# TH8_TEC_driver.net
KiCad netlist of a schematic drawn in Altium Designer
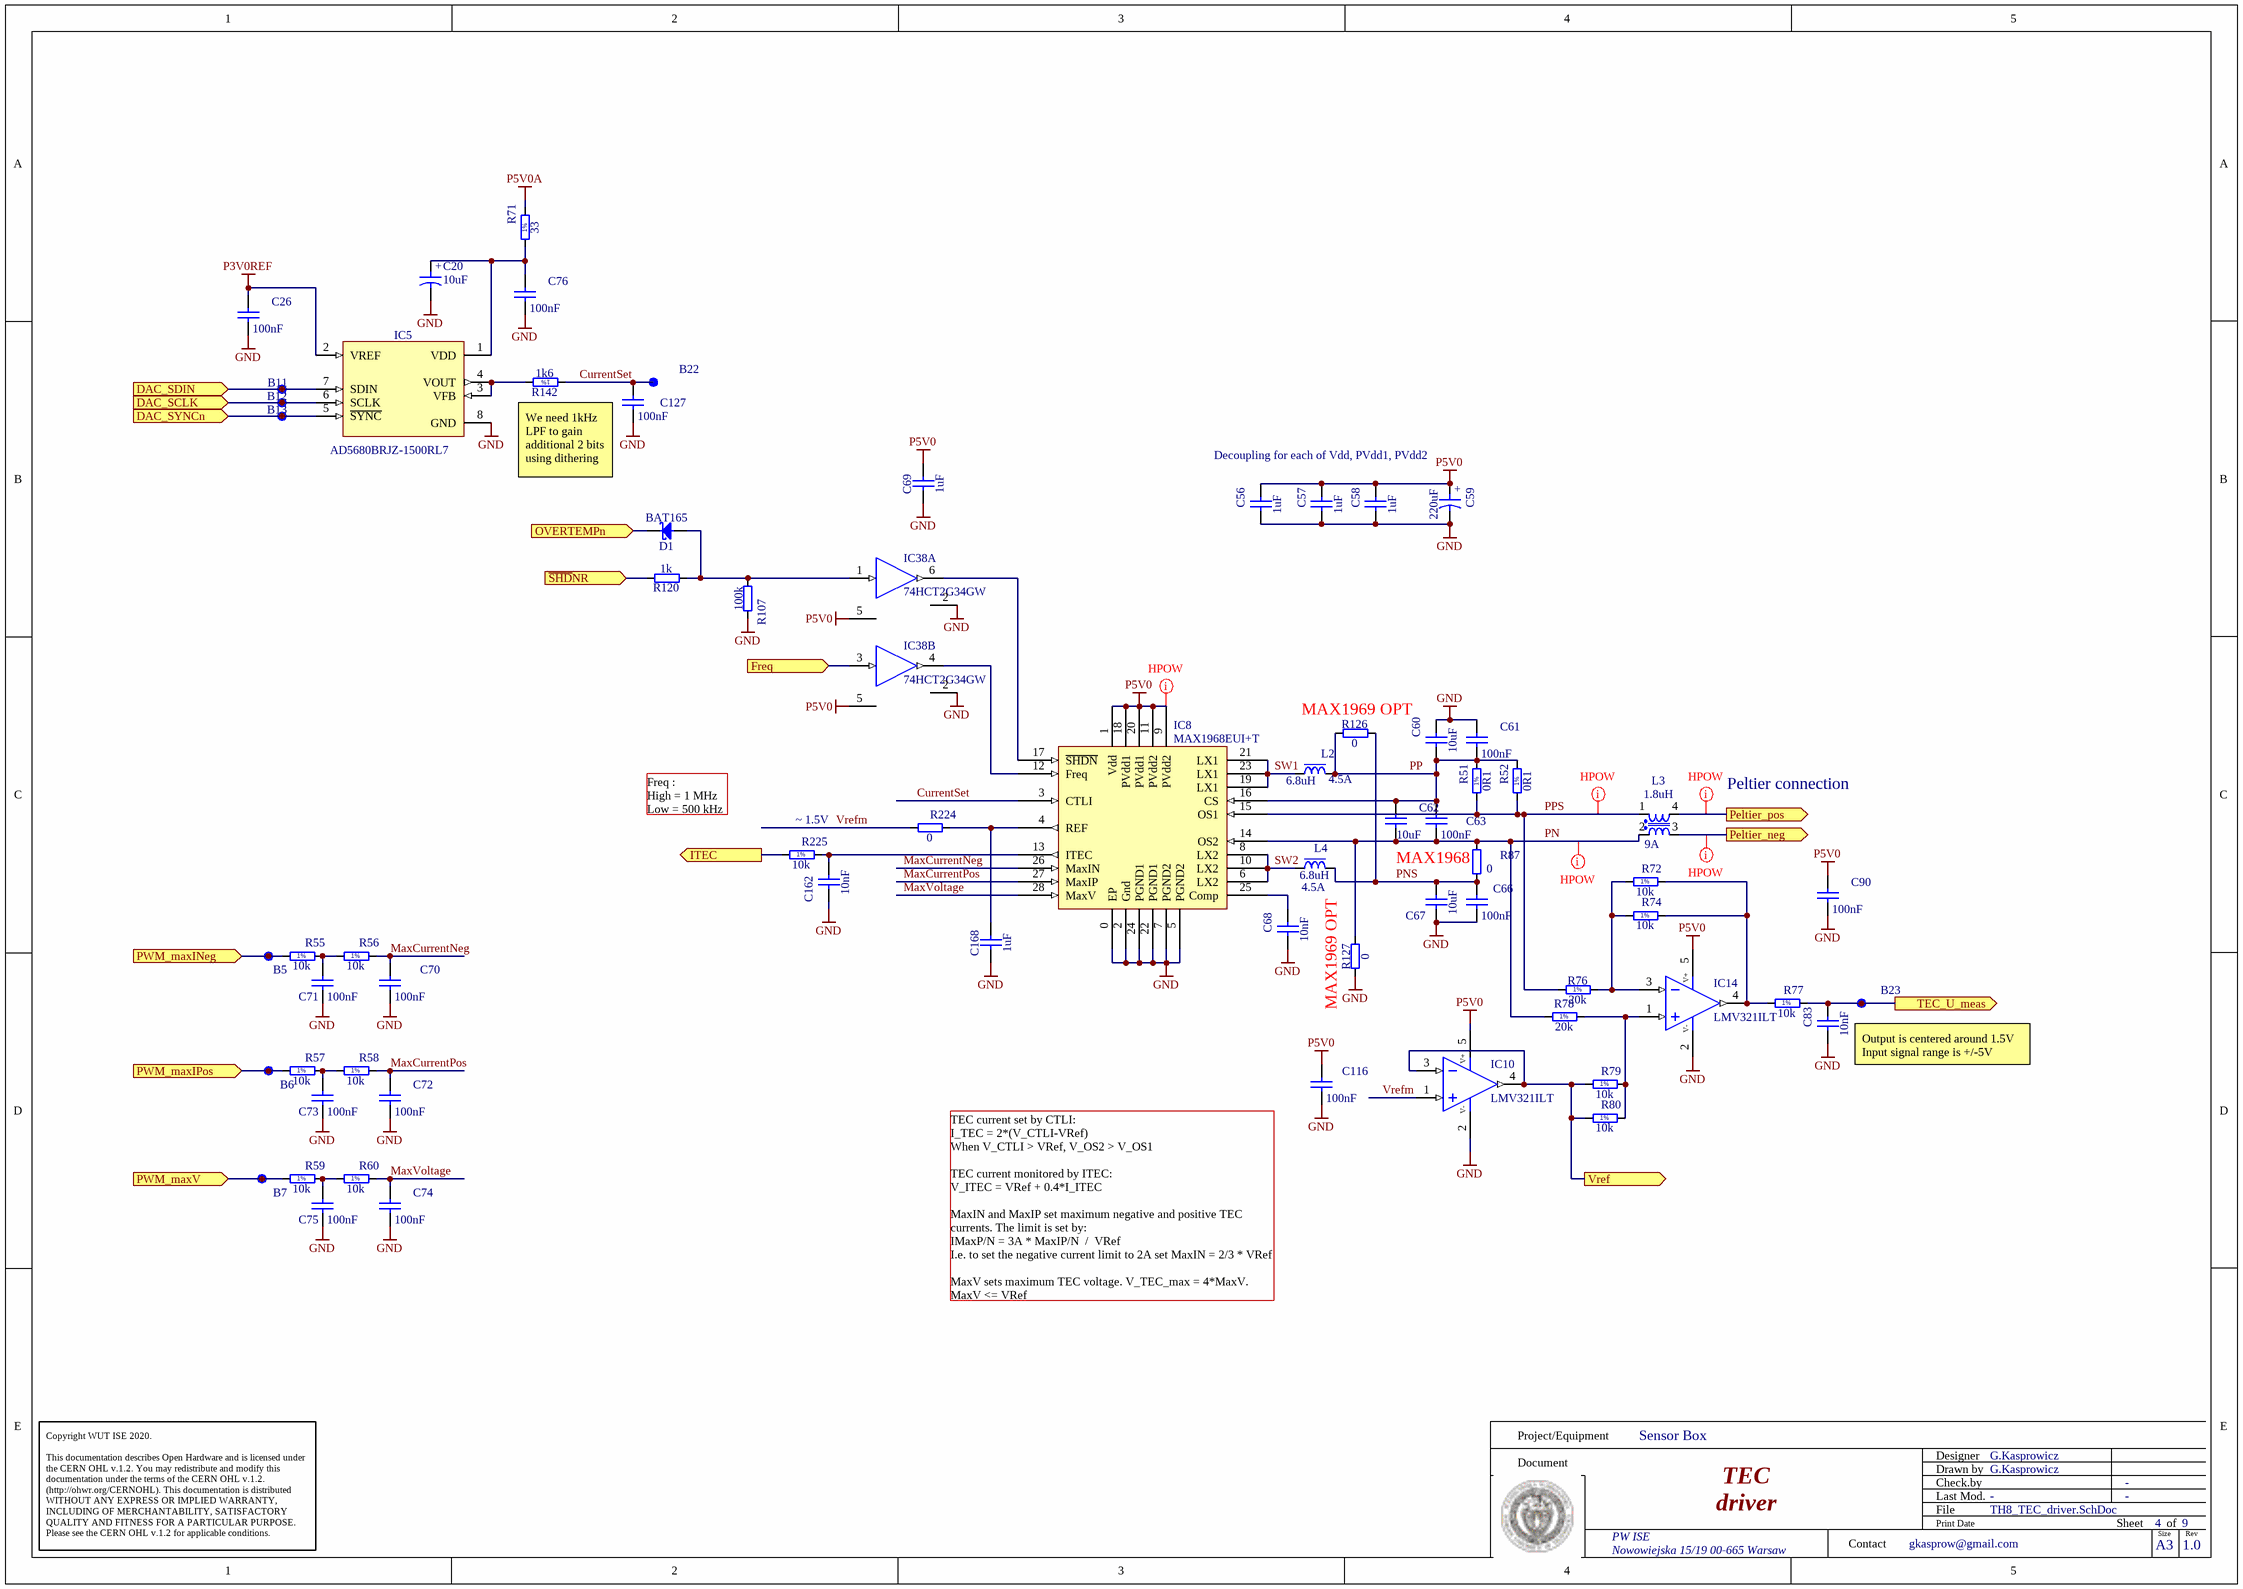
[diagram p0: TH8_TEC_driver.SchDoc]

(export (version "E")
  (design (tool "Eeschema 10.0.6"))
  (components
    (comp (ref "B5")
      (value "SMD Pad")
      (footprint "C100")
      (description "Through Hole Pad")
      (fields (field (name "PART NUMBER") "SMD_PAD_D1MM") (field (name "AUTHOR") "CERN DEM JLC"))
      (libsource (lib "Eletro-mechanical") (part "Single SMD Pad (Round)"))
    )
    (comp (ref "B6")
      (value "SMD Pad")
      (footprint "C100")
      (description "Through Hole Pad")
      (fields (field (name "PART NUMBER") "SMD_PAD_D1MM") (field (name "AUTHOR") "CERN DEM JLC"))
      (libsource (lib "Eletro-mechanical") (part "Single SMD Pad (Round)"))
    )
    (comp (ref "B7")
      (value "SMD Pad")
      (footprint "C100")
      (description "Through Hole Pad")
      (fields (field (name "PART NUMBER") "SMD_PAD_D1MM") (field (name "AUTHOR") "CERN DEM JLC"))
      (libsource (lib "Eletro-mechanical") (part "Single SMD Pad (Round)"))
    )
    (comp (ref "B11")
      (value "SMD Pad")
      (footprint "C100")
      (description "Through Hole Pad")
      (fields (field (name "PART NUMBER") "SMD_PAD_D1MM") (field (name "AUTHOR") "CERN DEM JLC"))
      (libsource (lib "Eletro-mechanical") (part "Single SMD Pad (Round)"))
    )
    (comp (ref "B12")
      (value "SMD Pad")
      (footprint "C100")
      (description "Through Hole Pad")
      (fields (field (name "PART NUMBER") "SMD_PAD_D1MM") (field (name "AUTHOR") "CERN DEM JLC"))
      (libsource (lib "Eletro-mechanical") (part "Single SMD Pad (Round)"))
    )
    (comp (ref "B13")
      (value "SMD Pad")
      (footprint "C100")
      (description "Through Hole Pad")
      (fields (field (name "PART NUMBER") "SMD_PAD_D1MM") (field (name "AUTHOR") "CERN DEM JLC"))
      (libsource (lib "Eletro-mechanical") (part "Single SMD Pad (Round)"))
    )
    (comp (ref "B22")
      (value "SMD Pad")
      (footprint "C100")
      (description "Through Hole Pad")
      (fields (field (name "PART NUMBER") "SMD_PAD_D1MM") (field (name "AUTHOR") "CERN DEM JLC"))
      (libsource (lib "Eletro-mechanical") (part "Single SMD Pad (Round)"))
    )
    (comp (ref "B23")
      (value "SMD Pad")
      (footprint "C100")
      (description "Through Hole Pad")
      (fields (field (name "PART NUMBER") "SMD_PAD_D1MM") (field (name "AUTHOR") "CERN DEM JLC"))
      (libsource (lib "Eletro-mechanical") (part "Single SMD Pad (Round)"))
    )
    (comp (ref "C20")
      (value "10uF")
      (footprint "CAPMP3216X180N")
      (description "Polarised capacitor")
      (fields
        (field (name "PART NUMBER") "CTE3216-18_10UF_16V_20%_AVX_TCJ")
        (field (name "VOLTAGE") "16V")
        (field (name "AUTHOR") "CERN DEM JLC")
      )
      (libsource (lib "Capacitors") (part "Capacitor - polarized"))
    )
    (comp (ref "C26")
      (value "100nF")
      (footprint "CAPC1005X55N")
      (description "Non-polarised capacitor")
      (fields
        (field (name "PART NUMBER") "CC0402_100NF_16V_10%_X5R")
        (field (name "VOLTAGE") "16V")
        (field (name "AUTHOR") "CERN DEM JLC")
      )
      (libsource (lib "Capacitors") (part "Capacitor - non polarized"))
    )
    (comp (ref "C56")
      (value "1uF")
      (footprint "CAPC1608X87N")
      (description "Non-polarised capacitor")
      (fields
        (field (name "PART NUMBER") "CC0603_1UF_25V_10%_X7R")
        (field (name "VOLTAGE") "25V")
        (field (name "AUTHOR") "CERN DEM JLC")
      )
      (libsource (lib "Capacitors") (part "Capacitor - non polarized"))
    )
    (comp (ref "C57")
      (value "1uF")
      (footprint "CAPC1608X87N")
      (description "Non-polarised capacitor")
      (fields
        (field (name "PART NUMBER") "CC0603_1UF_25V_10%_X7R")
        (field (name "VOLTAGE") "25V")
        (field (name "AUTHOR") "CERN DEM JLC")
      )
      (libsource (lib "Capacitors") (part "Capacitor - non polarized"))
    )
    (comp (ref "C58")
      (value "1uF")
      (footprint "CAPC1608X87N")
      (description "Non-polarised capacitor")
      (fields
        (field (name "PART NUMBER") "CC0603_1UF_25V_10%_X7R")
        (field (name "VOLTAGE") "25V")
        (field (name "AUTHOR") "CERN DEM JLC")
      )
      (libsource (lib "Capacitors") (part "Capacitor - non polarized"))
    )
    (comp (ref "C59")
      (value "220uF")
      (footprint "CAPMP7343X430N")
      (description "Polarised capacitor")
      (fields
        (field (name "PART NUMBER") "CTE7343-43_220UF_16V_10%")
        (field (name "VOLTAGE") "16V")
        (field (name "AUTHOR") "CERN DEM JLC")
      )
      (libsource (lib "Capacitors") (part "Capacitor - polarized"))
    )
    (comp (ref "C60")
      (value "10uF")
      (footprint "CAPC2012X135N")
      (description "Non-polarised capacitor")
      (fields
        (field (name "PART NUMBER") "CC0805_10UF_16V_10%_X5R")
        (field (name "VOLTAGE") "16V")
        (field (name "AUTHOR") "CERN DEM JLC")
      )
      (libsource (lib "Capacitors") (part "Capacitor - non polarized"))
    )
    (comp (ref "C61")
      (value "100nF")
      (footprint "CAPC1005X55N")
      (description "Non-polarised capacitor")
      (fields
        (field (name "PART NUMBER") "CC0402_100NF_16V_10%_X5R")
        (field (name "VOLTAGE") "16V")
        (field (name "AUTHOR") "CERN DEM JLC")
      )
      (libsource (lib "Capacitors") (part "Capacitor - non polarized"))
    )
    (comp (ref "C62")
      (value "10uF")
      (footprint "CAPC2012X135N")
      (description "Non-polarised capacitor")
      (fields
        (field (name "PART NUMBER") "CC0805_10UF_16V_10%_X5R")
        (field (name "VOLTAGE") "16V")
        (field (name "AUTHOR") "CERN DEM JLC")
      )
      (libsource (lib "Capacitors") (part "Capacitor - non polarized"))
    )
    (comp (ref "C63")
      (value "100nF")
      (footprint "CAPC1005X55N")
      (description "Non-polarised capacitor")
      (fields
        (field (name "PART NUMBER") "CC0402_100NF_16V_10%_X5R")
        (field (name "VOLTAGE") "16V")
        (field (name "AUTHOR") "CERN DEM JLC")
      )
      (libsource (lib "Capacitors") (part "Capacitor - non polarized"))
    )
    (comp (ref "C66")
      (value "100nF")
      (footprint "CAPC1005X55N")
      (description "Non-polarised capacitor")
      (fields
        (field (name "PART NUMBER") "CC0402_100NF_16V_10%_X5R")
        (field (name "VOLTAGE") "16V")
        (field (name "AUTHOR") "CERN DEM JLC")
      )
      (libsource (lib "Capacitors") (part "Capacitor - non polarized"))
    )
    (comp (ref "C67")
      (value "10uF")
      (footprint "CAPC2012X135N")
      (description "Non-polarised capacitor")
      (fields
        (field (name "PART NUMBER") "CC0805_10UF_16V_10%_X5R")
        (field (name "VOLTAGE") "16V")
        (field (name "AUTHOR") "CERN DEM JLC")
      )
      (libsource (lib "Capacitors") (part "Capacitor - non polarized"))
    )
    (comp (ref "C68")
      (value "10nF")
      (footprint "CAPC1005X55N")
      (description "Non-polarised capacitor")
      (fields
        (field (name "PART NUMBER") "CC0402_10NF_25V_10%_X7R")
        (field (name "VOLTAGE") "25V")
        (field (name "AUTHOR") "CERN DEM JLC")
      )
      (libsource (lib "Capacitors") (part "Capacitor - non polarized"))
    )
    (comp (ref "C69")
      (value "1uF")
      (footprint "CAPC1608X87N")
      (description "Non-polarised capacitor")
      (fields
        (field (name "PART NUMBER") "CC0603_1UF_25V_10%_X7R")
        (field (name "VOLTAGE") "25V")
        (field (name "AUTHOR") "CERN DEM JLC")
      )
      (libsource (lib "Capacitors") (part "Capacitor - non polarized"))
    )
    (comp (ref "C70")
      (value "100nF")
      (footprint "CAPC1005X55N")
      (description "Non-polarised capacitor")
      (fields
        (field (name "PART NUMBER") "CC0402_100NF_16V_10%_X5R")
        (field (name "VOLTAGE") "16V")
        (field (name "AUTHOR") "CERN DEM JLC")
      )
      (libsource (lib "Capacitors") (part "Capacitor - non polarized"))
    )
    (comp (ref "C71")
      (value "100nF")
      (footprint "CAPC1005X55N")
      (description "Non-polarised capacitor")
      (fields
        (field (name "PART NUMBER") "CC0402_100NF_16V_10%_X5R")
        (field (name "VOLTAGE") "16V")
        (field (name "AUTHOR") "CERN DEM JLC")
      )
      (libsource (lib "Capacitors") (part "Capacitor - non polarized"))
    )
    (comp (ref "C72")
      (value "100nF")
      (footprint "CAPC1005X55N")
      (description "Non-polarised capacitor")
      (fields
        (field (name "PART NUMBER") "CC0402_100NF_16V_10%_X5R")
        (field (name "VOLTAGE") "16V")
        (field (name "AUTHOR") "CERN DEM JLC")
      )
      (libsource (lib "Capacitors") (part "Capacitor - non polarized"))
    )
    (comp (ref "C73")
      (value "100nF")
      (footprint "CAPC1005X55N")
      (description "Non-polarised capacitor")
      (fields
        (field (name "PART NUMBER") "CC0402_100NF_16V_10%_X5R")
        (field (name "VOLTAGE") "16V")
        (field (name "AUTHOR") "CERN DEM JLC")
      )
      (libsource (lib "Capacitors") (part "Capacitor - non polarized"))
    )
    (comp (ref "C74")
      (value "100nF")
      (footprint "CAPC1005X55N")
      (description "Non-polarised capacitor")
      (fields
        (field (name "PART NUMBER") "CC0402_100NF_16V_10%_X5R")
        (field (name "VOLTAGE") "16V")
        (field (name "AUTHOR") "CERN DEM JLC")
      )
      (libsource (lib "Capacitors") (part "Capacitor - non polarized"))
    )
    (comp (ref "C75")
      (value "100nF")
      (footprint "CAPC1005X55N")
      (description "Non-polarised capacitor")
      (fields
        (field (name "PART NUMBER") "CC0402_100NF_16V_10%_X5R")
        (field (name "VOLTAGE") "16V")
        (field (name "AUTHOR") "CERN DEM JLC")
      )
      (libsource (lib "Capacitors") (part "Capacitor - non polarized"))
    )
    (comp (ref "C76")
      (value "100nF")
      (footprint "CAPC1005X55N")
      (description "Non-polarised capacitor")
      (fields
        (field (name "PART NUMBER") "CC0402_100NF_16V_10%_X5R")
        (field (name "VOLTAGE") "16V")
        (field (name "AUTHOR") "CERN DEM JLC")
      )
      (libsource (lib "Capacitors") (part "Capacitor - non polarized"))
    )
    (comp (ref "C83")
      (value "10nF")
      (footprint "CAPC1005X55N")
      (description "Non-polarised capacitor")
      (fields
        (field (name "PART NUMBER") "CC0402_10NF_25V_10%_X7R")
        (field (name "VOLTAGE") "25V")
        (field (name "AUTHOR") "CERN DEM JLC")
      )
      (libsource (lib "Capacitors") (part "Capacitor - non polarized"))
    )
    (comp (ref "C90")
      (value "100nF")
      (footprint "CAPC1005X55N")
      (description "Non-polarised capacitor")
      (fields
        (field (name "PART NUMBER") "CC0402_100NF_16V_10%_X5R")
        (field (name "VOLTAGE") "16V")
        (field (name "AUTHOR") "CERN DEM JLC")
      )
      (libsource (lib "Capacitors") (part "Capacitor - non polarized"))
    )
    (comp (ref "C116")
      (value "100nF")
      (footprint "CAPC1005X55N")
      (description "Non-polarised capacitor")
      (fields
        (field (name "PART NUMBER") "CC0402_100NF_16V_10%_X5R")
        (field (name "VOLTAGE") "16V")
        (field (name "AUTHOR") "CERN DEM JLC")
      )
      (libsource (lib "Capacitors") (part "Capacitor - non polarized"))
    )
    (comp (ref "C127")
      (value "100nF")
      (footprint "CAPC1005X55N")
      (description "Non-polarised capacitor")
      (fields
        (field (name "PART NUMBER") "CC0402_100NF_16V_10%_X5R")
        (field (name "VOLTAGE") "16V")
        (field (name "AUTHOR") "CERN DEM JLC")
      )
      (libsource (lib "Capacitors") (part "Capacitor - non polarized"))
    )
    (comp (ref "C162")
      (value "10nF")
      (footprint "CAPC1005X55N")
      (description "Non-polarised capacitor")
      (fields
        (field (name "PART NUMBER") "CC0402_10NF_25V_10%_X7R")
        (field (name "VOLTAGE") "25V")
        (field (name "AUTHOR") "CERN DEM JLC")
      )
      (libsource (lib "Capacitors") (part "Capacitor - non polarized"))
    )
    (comp (ref "C168")
      (value "1uF")
      (footprint "CAPC1608X87N")
      (description "Non-polarised capacitor")
      (fields
        (field (name "PART NUMBER") "CC0603_1UF_25V_10%_X7R")
        (field (name "VOLTAGE") "25V")
        (field (name "AUTHOR") "CERN DEM JLC")
      )
      (libsource (lib "Capacitors") (part "Capacitor - non polarized"))
    )
    (comp (ref "D1")
      (value "BAT165")
      (footprint "SOD2512X110N")
      (description "Schottky Diode")
      (fields
        (field (name "VOLTAGE") "40V")
        (field (name "POWER") "750mA")
        (field (name "AUTHOR") "CERN DEM JLC")
      )
      (libsource (lib "ICs And Semiconductors") (part "Diode Schottky"))
    )
    (comp (ref "IC5")
      (value "AD5680BRJZ-1500RL7")
      (footprint "SOT65P280X145-8N")
      (description "5V 18-Bit nanoDAC®in a SOT-23")
      (fields (field (name "MANUFACTURER") "ANALOG DEVICES") (field (name "AUTHOR") "GK"))
      (libsource (lib "LIBRARY_SCH") (part "DAC_AD5680BRJZ"))
    )
    (comp (ref "IC8")
      (value "MAX1968EUI+T")
      (footprint "TSSOP28-EP")
      (description "Power peltier driver. bipolar")
      (fields (field (name "PUBLISHER") "Altium Limited"))
      (libsource (lib "LIBRARY_SCH") (part "DRV_MAX1968"))
    )
    (comp (ref "IC10")
      (value "LMV321ILT")
      (footprint "SOT95P280X145-5N")
      (description "Operational Amplifier")
      (fields (field (name "MANUFACTURER") "ST MICROELECTRONICS") (field (name "AUTHOR") "CERN DEM MR"))
      (libsource (lib "ICs And Semiconductors") (part "Operational Amplifier Type10"))
    )
    (comp (ref "IC14")
      (value "LMV321ILT")
      (footprint "SOT95P280X145-5N")
      (description "Operational Amplifier")
      (fields (field (name "MANUFACTURER") "ST MICROELECTRONICS") (field (name "AUTHOR") "CERN DEM MR"))
      (libsource (lib "ICs And Semiconductors") (part "Operational Amplifier Type10"))
    )
    (comp (ref "IC38")
      (value "74HCT2G34GW")
      (footprint "SOT65P210X110-6N")
      (description "Dual Buffer Gate")
      (fields (field (name "MANUFACTURER") "TEXAS INSTRUMENTS") (field (name "AUTHOR") "GK"))
      (libsource (lib "ICS-logic") (part "74HCT2G34GW"))
    )
    (comp (ref "L2")
      (value "6.8uH")
      (footprint "INDM6965X300N")
      (description "Inductor With Core")
      (fields
        (field (name "PART NUMBER") "IND2525_6.8UH_20%_VISHAY_IHLP-2525CZ-01")
        (field (name "POWER") "4.5A")
        (field (name "TOLERANCE") "±20%")
        (field (name "AUTHOR") "CERN DEM MR")
      )
      (libsource (lib "Inductors & Transformers") (part "Inductor With Magnetic core"))
    )
    (comp (ref "L3")
      (value "1.8uH")
      (footprint "IND_PULSE_PA4339")
      (description "1.8uH 9A 10mR CMC")
      (fields
        (field (name "PART NUMBER") "PA4339.101NLT")
        (field (name "TOLERANCE") "±50%")
        (field (name "POWER") "9A")
        (field (name "AUTHOR") "GK")
      )
      (libsource (lib "Inductors_Transformers") (part "L_CMC_PA4339.101NLT"))
    )
    (comp (ref "L4")
      (value "6.8uH")
      (footprint "INDM6965X300N")
      (description "Inductor With Core")
      (fields
        (field (name "PART NUMBER") "IND2525_6.8UH_20%_VISHAY_IHLP-2525CZ-01")
        (field (name "POWER") "4.5A")
        (field (name "TOLERANCE") "±20%")
        (field (name "AUTHOR") "CERN DEM MR")
      )
      (libsource (lib "Inductors & Transformers") (part "Inductor With Magnetic core"))
    )
    (comp (ref "R51")
      (value "0R1")
      (footprint "RESC3216X65N")
      (description "Resistor - 1%")
      (fields
        (field (name "PART NUMBER") "R1206_0R1_1%_0.25W_100PPM_YAGEO_PT")
        (field (name "POWER") "0.25W")
        (field (name "AUTHOR") "CERN DEM JMW")
      )
      (libsource (lib "Resistors") (part "Resistor - 1%"))
    )
    (comp (ref "R52")
      (value "0R1")
      (footprint "RESC3216X65N")
      (description "Resistor - 1%")
      (fields
        (field (name "PART NUMBER") "R1206_0R1_1%_0.25W_100PPM_YAGEO_PT")
        (field (name "POWER") "0.25W")
        (field (name "AUTHOR") "CERN DEM JMW")
      )
      (libsource (lib "Resistors") (part "Resistor - 1%"))
    )
    (comp (ref "R55")
      (value "10k")
      (footprint "RESC1005X40N")
      (description "Resistor - 1%")
      (fields
        (field (name "PART NUMBER") "R0402_10K_1%_0.0625W_100PPM")
        (field (name "POWER") "0.0625W")
        (field (name "AUTHOR") "CERN DEM JLC")
      )
      (libsource (lib "Resistors") (part "Resistor - 1%"))
    )
    (comp (ref "R56")
      (value "10k")
      (footprint "RESC1005X40N")
      (description "Resistor - 1%")
      (fields
        (field (name "PART NUMBER") "R0402_10K_1%_0.0625W_100PPM")
        (field (name "POWER") "0.0625W")
        (field (name "AUTHOR") "CERN DEM JLC")
      )
      (libsource (lib "Resistors") (part "Resistor - 1%"))
    )
    (comp (ref "R57")
      (value "10k")
      (footprint "RESC1005X40N")
      (description "Resistor - 1%")
      (fields
        (field (name "PART NUMBER") "R0402_10K_1%_0.0625W_100PPM")
        (field (name "POWER") "0.0625W")
        (field (name "AUTHOR") "CERN DEM JLC")
      )
      (libsource (lib "Resistors") (part "Resistor - 1%"))
    )
    (comp (ref "R58")
      (value "10k")
      (footprint "RESC1005X40N")
      (description "Resistor - 1%")
      (fields
        (field (name "PART NUMBER") "R0402_10K_1%_0.0625W_100PPM")
        (field (name "POWER") "0.0625W")
        (field (name "AUTHOR") "CERN DEM JLC")
      )
      (libsource (lib "Resistors") (part "Resistor - 1%"))
    )
    (comp (ref "R59")
      (value "10k")
      (footprint "RESC1005X40N")
      (description "Resistor - 1%")
      (fields
        (field (name "PART NUMBER") "R0402_10K_1%_0.0625W_100PPM")
        (field (name "POWER") "0.0625W")
        (field (name "AUTHOR") "CERN DEM JLC")
      )
      (libsource (lib "Resistors") (part "Resistor - 1%"))
    )
    (comp (ref "R60")
      (value "10k")
      (footprint "RESC1005X40N")
      (description "Resistor - 1%")
      (fields
        (field (name "PART NUMBER") "R0402_10K_1%_0.0625W_100PPM")
        (field (name "POWER") "0.0625W")
        (field (name "AUTHOR") "CERN DEM JLC")
      )
      (libsource (lib "Resistors") (part "Resistor - 1%"))
    )
    (comp (ref "R71")
      (value "33")
      (footprint "RESC1005X40N")
      (description "Resistor - 1%")
      (fields
        (field (name "PART NUMBER") "R0402_33R_1%_0.0625W_100PPM")
        (field (name "POWER") "0.0625W")
        (field (name "AUTHOR") "CERN DEM JLC")
      )
      (libsource (lib "Resistors") (part "Resistor - 1%"))
    )
    (comp (ref "R72")
      (value "10k")
      (footprint "RESC1005X40N")
      (description "Resistor - 1%")
      (fields
        (field (name "PART NUMBER") "R0402_10K_1%_0.0625W_100PPM")
        (field (name "POWER") "0.0625W")
        (field (name "AUTHOR") "CERN DEM JLC")
      )
      (libsource (lib "Resistors") (part "Resistor - 1%"))
    )
    (comp (ref "R74")
      (value "10k")
      (footprint "RESC1005X40N")
      (description "Resistor - 1%")
      (fields
        (field (name "PART NUMBER") "R0402_10K_1%_0.0625W_100PPM")
        (field (name "POWER") "0.0625W")
        (field (name "AUTHOR") "CERN DEM JLC")
      )
      (libsource (lib "Resistors") (part "Resistor - 1%"))
    )
    (comp (ref "R76")
      (value "20k")
      (footprint "RESC1005X40N")
      (description "Resistor - 1%")
      (fields
        (field (name "PART NUMBER") "R0402_20K_1%_0.0625W_100PPM")
        (field (name "POWER") "0.0625W")
        (field (name "AUTHOR") "CERN DEM JLC")
      )
      (libsource (lib "Resistors") (part "Resistor - 1%"))
    )
    (comp (ref "R77")
      (value "10k")
      (footprint "RESC1005X40N")
      (description "Resistor - 1%")
      (fields
        (field (name "PART NUMBER") "R0402_10K_1%_0.0625W_100PPM")
        (field (name "POWER") "0.0625W")
        (field (name "AUTHOR") "CERN DEM JLC")
      )
      (libsource (lib "Resistors") (part "Resistor - 1%"))
    )
    (comp (ref "R78")
      (value "20k")
      (footprint "RESC1005X40N")
      (description "Resistor - 1%")
      (fields
        (field (name "PART NUMBER") "R0402_20K_1%_0.0625W_100PPM")
        (field (name "POWER") "0.0625W")
        (field (name "AUTHOR") "CERN DEM JLC")
      )
      (libsource (lib "Resistors") (part "Resistor - 1%"))
    )
    (comp (ref "R79")
      (value "10k")
      (footprint "RESC1005X40N")
      (description "Resistor - 1%")
      (fields
        (field (name "PART NUMBER") "R0402_10K_1%_0.0625W_100PPM")
        (field (name "POWER") "0.0625W")
        (field (name "AUTHOR") "CERN DEM JLC")
      )
      (libsource (lib "Resistors") (part "Resistor - 1%"))
    )
    (comp (ref "R80")
      (value "10k")
      (footprint "RESC1005X40N")
      (description "Resistor - 1%")
      (fields
        (field (name "PART NUMBER") "R0402_10K_1%_0.0625W_100PPM")
        (field (name "POWER") "0.0625W")
        (field (name "AUTHOR") "CERN DEM JLC")
      )
      (libsource (lib "Resistors") (part "Resistor - 1%"))
    )
    (comp (ref "R87")
      (value "0")
      (footprint "RESC3116X80N")
      (description "Resistor")
      (fields
        (field (name "PART NUMBER") "R1206_0R_JUMPER_SEI_HCJ")
        (field (name "MANUFACTURER") "SEI (STACKPOLE ELECTRONICS INC.)")
        (field (name "AUTHOR") "CERN DEM MR")
      )
      (libsource (lib "Resistors") (part "Resistor"))
    )
    (comp (ref "R107")
      (value "100k")
      (footprint "RESC1005X40N")
      (description "Resistor - 1%")
      (fields
        (field (name "PART NUMBER") "R0402_100K_1%_0.0625W_100PPM")
        (field (name "POWER") "0.0625W")
        (field (name "AUTHOR") "CERN DEM JLC")
      )
      (libsource (lib "Resistors") (part "Resistor - 1%"))
    )
    (comp (ref "R120")
      (value "1k")
      (footprint "RESC1005X40N")
      (description "Resistor - 1%")
      (fields
        (field (name "PART NUMBER") "R0402_1K_1%_0.0625W_100PPM")
        (field (name "POWER") "0.0625W")
        (field (name "AUTHOR") "CERN DEM JLC")
      )
      (libsource (lib "Resistors") (part "Resistor - 1%"))
    )
    (comp (ref "R126")
      (value "0")
      (footprint "RESC3116X80N")
      (description "Resistor")
      (fields
        (field (name "PART NUMBER") "R1206_0R_JUMPER_SEI_HCJ")
        (field (name "MANUFACTURER") "SEI (STACKPOLE ELECTRONICS INC.)")
        (field (name "AUTHOR") "CERN DEM MR")
      )
      (libsource (lib "Resistors") (part "Resistor"))
    )
    (comp (ref "R127")
      (value "0")
      (footprint "RESC3116X80N")
      (description "Resistor")
      (fields
        (field (name "PART NUMBER") "R1206_0R_JUMPER_SEI_HCJ")
        (field (name "MANUFACTURER") "SEI (STACKPOLE ELECTRONICS INC.)")
        (field (name "AUTHOR") "CERN DEM MR")
      )
      (libsource (lib "Resistors") (part "Resistor"))
    )
    (comp (ref "R142")
      (value "1k6")
      (footprint "RESC1005X40N")
      (description "Resistor - 1%")
      (fields
        (field (name "PART NUMBER") "R0402_1K6_1%_0.0625W_100PPM")
        (field (name "POWER") "0.0625W")
        (field (name "AUTHOR") "CERN DEM JLC")
      )
      (libsource (lib "Resistors") (part "Resistor - 1%"))
    )
    (comp (ref "R224")
      (value "0")
      (footprint "RESC1005X40N")
      (description "Resistor")
      (fields
        (field (name "PART NUMBER") "R0402_0R_JUMPER")
        (field (name "MANUFACTURER") "GENERIC")
        (field (name "AUTHOR") "CERN DEM JLC")
      )
      (libsource (lib "Resistors") (part "Resistor"))
    )
    (comp (ref "R225")
      (value "10k")
      (footprint "RESC1005X40N")
      (description "Resistor - 1%")
      (fields
        (field (name "PART NUMBER") "R0402_10K_1%_0.0625W_100PPM")
        (field (name "POWER") "0.0625W")
        (field (name "AUTHOR") "CERN DEM JLC")
      )
      (libsource (lib "Resistors") (part "Resistor - 1%"))
    )
  )
  (nets
    (net (code "1") (name "/CurrentSet") (class "Default")
      (node (ref "B22") (pin "1") (pinfunction "1_1") (pintype "bidirectional"))
      (node (ref "C127") (pin "1") (pinfunction "1_1") (pintype "passive"))
      (node (ref "IC8") (pin "3") (pinfunction "CTLI_3") (pintype "input"))
      (node (ref "R142") (pin "1") (pinfunction "1_1") (pintype "passive"))
    )
    (net (code "2") (name "/DAC_SCLK") (class "Default")
      (node (ref "B12") (pin "1") (pinfunction "1_1") (pintype "bidirectional"))
      (node (ref "IC5") (pin "6") (pinfunction "SCLK_6") (pintype "input"))
    )
    (net (code "3") (name "/DAC_SDIN") (class "Default")
      (node (ref "B11") (pin "1") (pinfunction "1_1") (pintype "bidirectional"))
      (node (ref "IC5") (pin "7") (pinfunction "SDIN_7") (pintype "input"))
    )
    (net (code "4") (name "/DAC_SYNCn") (class "Default")
      (node (ref "B13") (pin "1") (pinfunction "1_1") (pintype "bidirectional"))
      (node (ref "IC5") (pin "5") (pinfunction "~{SYNC}_5") (pintype "input"))
    )
    (net (code "5") (name "/Freq") (class "Default")
      (node (ref "IC38") (pin "3") (pinfunction "2A_3") (pintype "input"))
    )
    (net (code "6") (name "/ITEC") (class "Default")
      (node (ref "R225") (pin "1") (pinfunction "1_1") (pintype "passive"))
    )
    (net (code "7") (name "/MaxCurrentNeg") (class "Default")
      (node (ref "C70") (pin "1") (pinfunction "1_1") (pintype "passive"))
      (node (ref "IC8") (pin "26") (pinfunction "MaxIN_26") (pintype "input"))
      (node (ref "R56") (pin "2") (pinfunction "2_2") (pintype "passive"))
    )
    (net (code "8") (name "/MaxCurrentPos") (class "Default")
      (node (ref "C72") (pin "1") (pinfunction "1_1") (pintype "passive"))
      (node (ref "IC8") (pin "27") (pinfunction "MaxIP_27") (pintype "input"))
      (node (ref "R58") (pin "2") (pinfunction "2_2") (pintype "passive"))
    )
    (net (code "9") (name "/MaxVoltage") (class "Default")
      (node (ref "C74") (pin "1") (pinfunction "1_1") (pintype "passive"))
      (node (ref "IC8") (pin "28") (pinfunction "MaxV_28") (pintype "input"))
      (node (ref "R60") (pin "2") (pinfunction "2_2") (pintype "passive"))
    )
    (net (code "10") (name "/OVERTEMPn") (class "Default")
      (node (ref "D1") (pin "1") (pinfunction "C_1") (pintype "passive"))
    )
    (net (code "11") (name "/PN") (class "Default")
      (node (ref "C62") (pin "1") (pinfunction "1_1") (pintype "passive"))
      (node (ref "C63") (pin "2") (pinfunction "2_2") (pintype "passive"))
      (node (ref "IC8") (pin "14") (pinfunction "OS2_14") (pintype "input"))
      (node (ref "L3") (pin "2") (pinfunction "2_2") (pintype "passive"))
      (node (ref "R127") (pin "2") (pinfunction "2_2") (pintype "passive"))
      (node (ref "R78") (pin "1") (pinfunction "1_1") (pintype "passive"))
      (node (ref "R87") (pin "2") (pinfunction "2_2") (pintype "passive"))
    )
    (net (code "12") (name "/PNS") (class "Default")
      (node (ref "C66") (pin "1") (pinfunction "1_1") (pintype "passive"))
      (node (ref "C67") (pin "2") (pinfunction "2_2") (pintype "passive"))
      (node (ref "L4") (pin "2") (pinfunction "2_2") (pintype "passive"))
      (node (ref "R126") (pin "2") (pinfunction "2_2") (pintype "passive"))
      (node (ref "R87") (pin "1") (pinfunction "1_1") (pintype "passive"))
    )
    (net (code "13") (name "/PP") (class "Default")
      (node (ref "C60") (pin "1") (pinfunction "1_1") (pintype "passive"))
      (node (ref "C61") (pin "2") (pinfunction "2_2") (pintype "passive"))
      (node (ref "C62") (pin "2") (pinfunction "2_2") (pintype "passive"))
      (node (ref "C63") (pin "1") (pinfunction "1_1") (pintype "passive"))
      (node (ref "IC8") (pin "16") (pinfunction "CS_16") (pintype "input"))
      (node (ref "L2") (pin "2") (pinfunction "2_2") (pintype "passive"))
      (node (ref "R126") (pin "1") (pinfunction "1_1") (pintype "passive"))
      (node (ref "R51") (pin "2") (pinfunction "2_2") (pintype "passive"))
      (node (ref "R52") (pin "2") (pinfunction "2_2") (pintype "passive"))
    )
    (net (code "14") (name "/PPS") (class "Default")
      (node (ref "IC8") (pin "15") (pinfunction "OS1_15") (pintype "input"))
      (node (ref "L3") (pin "1") (pinfunction "1_1") (pintype "passive"))
      (node (ref "R51") (pin "1") (pinfunction "1_1") (pintype "passive"))
      (node (ref "R52") (pin "1") (pinfunction "1_1") (pintype "passive"))
      (node (ref "R76") (pin "1") (pinfunction "1_1") (pintype "passive"))
    )
    (net (code "15") (name "/PWM_maxINeg") (class "Default")
      (node (ref "B5") (pin "1") (pinfunction "1_1") (pintype "bidirectional"))
      (node (ref "R55") (pin "1") (pinfunction "1_1") (pintype "passive"))
    )
    (net (code "16") (name "/PWM_maxIPos") (class "Default")
      (node (ref "B6") (pin "1") (pinfunction "1_1") (pintype "bidirectional"))
      (node (ref "R57") (pin "1") (pinfunction "1_1") (pintype "passive"))
    )
    (net (code "17") (name "/PWM_maxV") (class "Default")
      (node (ref "B7") (pin "1") (pinfunction "1_1") (pintype "bidirectional"))
      (node (ref "R59") (pin "1") (pinfunction "1_1") (pintype "passive"))
    )
    (net (code "18") (name "/Peltier_neg") (class "Default")
      (node (ref "L3") (pin "3") (pinfunction "3_3") (pintype "passive"))
    )
    (net (code "19") (name "/Peltier_pos") (class "Default")
      (node (ref "L3") (pin "4") (pinfunction "4_4") (pintype "passive"))
    )
    (net (code "20") (name "/SW1") (class "Default")
      (node (ref "IC8") (pin "19") (pinfunction "LX1_19") (pintype "power_in"))
      (node (ref "IC8") (pin "21") (pinfunction "LX1_21") (pintype "power_in"))
      (node (ref "IC8") (pin "23") (pinfunction "LX1_23") (pintype "power_in"))
      (node (ref "L2") (pin "1") (pinfunction "1_1") (pintype "passive"))
    )
    (net (code "21") (name "/SW2") (class "Default")
      (node (ref "IC8") (pin "10") (pinfunction "LX2_10") (pintype "power_in"))
      (node (ref "IC8") (pin "6") (pinfunction "LX2_6") (pintype "power_in"))
      (node (ref "IC8") (pin "8") (pinfunction "LX2_8") (pintype "power_in"))
      (node (ref "L4") (pin "1") (pinfunction "1_1") (pintype "passive"))
    )
    (net (code "22") (name "/TEC_U_meas") (class "Default")
      (node (ref "B23") (pin "1") (pinfunction "1_1") (pintype "bidirectional"))
      (node (ref "C83") (pin "2") (pinfunction "2_2") (pintype "passive"))
      (node (ref "R77") (pin "2") (pinfunction "2_2") (pintype "passive"))
    )
    (net (code "23") (name "/Vref") (class "Default")
      (node (ref "IC10") (pin "3") (pinfunction "IN-_3") (pintype "input"))
      (node (ref "IC10") (pin "4") (pinfunction "OUT_4") (pintype "output"))
      (node (ref "R79") (pin "1") (pinfunction "1_1") (pintype "passive"))
      (node (ref "R80") (pin "1") (pinfunction "1_1") (pintype "passive"))
    )
    (net (code "24") (name "/Vrefm") (class "Default")
      (node (ref "IC10") (pin "1") (pinfunction "IN+_1") (pintype "input"))
      (node (ref "R224") (pin "1") (pinfunction "1_1") (pintype "passive"))
    )
    (net (code "25") (name "/~{SHD}NR") (class "Default")
      (node (ref "R120") (pin "2") (pinfunction "2_2") (pintype "passive"))
    )
    (net (code "26") (name "GND") (class "Default")
      (node (ref "C116") (pin "2") (pinfunction "2_2") (pintype "passive"))
      (node (ref "C127") (pin "2") (pinfunction "2_2") (pintype "passive"))
      (node (ref "C162") (pin "1") (pinfunction "1_1") (pintype "passive"))
      (node (ref "C168") (pin "1") (pinfunction "1_1") (pintype "passive"))
      (node (ref "C20") (pin "2") (pinfunction "2_2") (pintype "passive"))
      (node (ref "C26") (pin "2") (pinfunction "2_2") (pintype "passive"))
      (node (ref "C56") (pin "1") (pinfunction "1_1") (pintype "passive"))
      (node (ref "C57") (pin "1") (pinfunction "1_1") (pintype "passive"))
      (node (ref "C58") (pin "1") (pinfunction "1_1") (pintype "passive"))
      (node (ref "C59") (pin "2") (pinfunction "2_2") (pintype "passive"))
      (node (ref "C60") (pin "2") (pinfunction "2_2") (pintype "passive"))
      (node (ref "C61") (pin "1") (pinfunction "1_1") (pintype "passive"))
      (node (ref "C66") (pin "2") (pinfunction "2_2") (pintype "passive"))
      (node (ref "C67") (pin "1") (pinfunction "1_1") (pintype "passive"))
      (node (ref "C68") (pin "1") (pinfunction "1_1") (pintype "passive"))
      (node (ref "C69") (pin "1") (pinfunction "1_1") (pintype "passive"))
      (node (ref "C70") (pin "2") (pinfunction "2_2") (pintype "passive"))
      (node (ref "C71") (pin "2") (pinfunction "2_2") (pintype "passive"))
      (node (ref "C72") (pin "2") (pinfunction "2_2") (pintype "passive"))
      (node (ref "C73") (pin "2") (pinfunction "2_2") (pintype "passive"))
      (node (ref "C74") (pin "2") (pinfunction "2_2") (pintype "passive"))
      (node (ref "C75") (pin "2") (pinfunction "2_2") (pintype "passive"))
      (node (ref "C76") (pin "2") (pinfunction "2_2") (pintype "passive"))
      (node (ref "C83") (pin "1") (pinfunction "1_1") (pintype "passive"))
      (node (ref "C90") (pin "2") (pinfunction "2_2") (pintype "passive"))
      (node (ref "IC10") (pin "2") (pinfunction "V-_2") (pintype "power_in"))
      (node (ref "IC14") (pin "2") (pinfunction "V-_2") (pintype "power_in"))
      (node (ref "IC38") (pin "2") (pinfunction "GND_2") (pintype "power_in"))
      (node (ref "IC5") (pin "8") (pinfunction "GND_8") (pintype "power_in"))
      (node (ref "IC8") (pin "0") (pinfunction "EP_0") (pintype "passive"))
      (node (ref "IC8") (pin "2") (pinfunction "Gnd_2") (pintype "power_in"))
      (node (ref "IC8") (pin "22") (pinfunction "PGND1_22") (pintype "power_in"))
      (node (ref "IC8") (pin "24") (pinfunction "PGND1_24") (pintype "power_in"))
      (node (ref "IC8") (pin "5") (pinfunction "PGND2_5") (pintype "power_in"))
      (node (ref "IC8") (pin "7") (pinfunction "PGND2_7") (pintype "power_in"))
      (node (ref "R107") (pin "2") (pinfunction "2_2") (pintype "passive"))
      (node (ref "R127") (pin "1") (pinfunction "1_1") (pintype "passive"))
    )
    (net (code "27") (name "Net-(C71-Pad1)") (class "Default")
      (node (ref "C71") (pin "1") (pinfunction "1_1") (pintype "passive"))
      (node (ref "R55") (pin "2") (pinfunction "2_2") (pintype "passive"))
      (node (ref "R56") (pin "1") (pinfunction "1_1") (pintype "passive"))
    )
    (net (code "28") (name "Net-(C73-Pad1)") (class "Default")
      (node (ref "C73") (pin "1") (pinfunction "1_1") (pintype "passive"))
      (node (ref "R57") (pin "2") (pinfunction "2_2") (pintype "passive"))
      (node (ref "R58") (pin "1") (pinfunction "1_1") (pintype "passive"))
    )
    (net (code "29") (name "Net-(C75-Pad1)") (class "Default")
      (node (ref "C75") (pin "1") (pinfunction "1_1") (pintype "passive"))
      (node (ref "R59") (pin "2") (pinfunction "2_2") (pintype "passive"))
      (node (ref "R60") (pin "1") (pinfunction "1_1") (pintype "passive"))
    )
    (net (code "30") (name "Net-(D1-A)") (class "Default")
      (node (ref "D1") (pin "2") (pinfunction "A_2") (pintype "passive"))
      (node (ref "IC38") (pin "1") (pinfunction "1A_1") (pintype "input"))
      (node (ref "R107") (pin "1") (pinfunction "1_1") (pintype "passive"))
      (node (ref "R120") (pin "1") (pinfunction "1_1") (pintype "passive"))
    )
    (net (code "31") (name "Net-(IC5-VDD)") (class "Default")
      (node (ref "C20") (pin "1") (pinfunction "1_1") (pintype "passive"))
      (node (ref "C76") (pin "1") (pinfunction "1_1") (pintype "passive"))
      (node (ref "IC5") (pin "1") (pinfunction "VDD_1") (pintype "power_in"))
      (node (ref "R71") (pin "1") (pinfunction "1_1") (pintype "passive"))
    )
    (net (code "32") (name "Net-(IC5-VFB)") (class "Default")
      (node (ref "IC5") (pin "3") (pinfunction "VFB_3") (pintype "input"))
      (node (ref "IC5") (pin "4") (pinfunction "VOUT_4") (pintype "output"))
      (node (ref "R142") (pin "2") (pinfunction "2_2") (pintype "passive"))
    )
    (net (code "33") (name "Net-(IC8-Comp)") (class "Default")
      (node (ref "C68") (pin "2") (pinfunction "2_2") (pintype "passive"))
      (node (ref "IC8") (pin "25") (pinfunction "Comp_25") (pintype "passive"))
    )
    (net (code "34") (name "Net-(IC8-ITEC)") (class "Default")
      (node (ref "C162") (pin "2") (pinfunction "2_2") (pintype "passive"))
      (node (ref "IC8") (pin "13") (pinfunction "ITEC_13") (pintype "output"))
      (node (ref "R225") (pin "2") (pinfunction "2_2") (pintype "passive"))
    )
    (net (code "35") (name "Net-(IC8-REF)") (class "Default")
      (node (ref "C168") (pin "2") (pinfunction "2_2") (pintype "passive"))
      (node (ref "IC8") (pin "4") (pinfunction "REF_4") (pintype "output"))
      (node (ref "R224") (pin "2") (pinfunction "2_2") (pintype "passive"))
    )
    (net (code "36") (name "Net-(IC14-IN+)") (class "Default")
      (node (ref "IC14") (pin "1") (pinfunction "IN+_1") (pintype "input"))
      (node (ref "R78") (pin "2") (pinfunction "2_2") (pintype "passive"))
      (node (ref "R79") (pin "2") (pinfunction "2_2") (pintype "passive"))
      (node (ref "R80") (pin "2") (pinfunction "2_2") (pintype "passive"))
    )
    (net (code "37") (name "Net-(IC14-IN-)") (class "Default")
      (node (ref "IC14") (pin "3") (pinfunction "IN-_3") (pintype "input"))
      (node (ref "R72") (pin "1") (pinfunction "1_1") (pintype "passive"))
      (node (ref "R74") (pin "1") (pinfunction "1_1") (pintype "passive"))
      (node (ref "R76") (pin "2") (pinfunction "2_2") (pintype "passive"))
    )
    (net (code "38") (name "Net-(IC14-OUT)") (class "Default")
      (node (ref "IC14") (pin "4") (pinfunction "OUT_4") (pintype "output"))
      (node (ref "R72") (pin "2") (pinfunction "2_2") (pintype "passive"))
      (node (ref "R74") (pin "2") (pinfunction "2_2") (pintype "passive"))
      (node (ref "R77") (pin "1") (pinfunction "1_1") (pintype "passive"))
    )
    (net (code "39") (name "Net-(IC38A-1Y)") (class "Default")
      (node (ref "IC38") (pin "6") (pinfunction "1Y_6") (pintype "output"))
      (node (ref "IC8") (pin "17") (pinfunction "~{SHDN}_17") (pintype "input"))
    )
    (net (code "40") (name "Net-(IC38B-2Y)") (class "Default")
      (node (ref "IC38") (pin "4") (pinfunction "2Y_4") (pintype "output"))
      (node (ref "IC8") (pin "12") (pinfunction "Freq_12") (pintype "input"))
    )
    (net (code "41") (name "P3V0REF") (class "Default")
      (node (ref "C26") (pin "1") (pinfunction "1_1") (pintype "passive"))
      (node (ref "IC5") (pin "2") (pinfunction "VREF_2") (pintype "input"))
    )
    (net (code "42") (name "P5V0") (class "Default")
      (node (ref "C116") (pin "1") (pinfunction "1_1") (pintype "passive"))
      (node (ref "C56") (pin "2") (pinfunction "2_2") (pintype "passive"))
      (node (ref "C57") (pin "2") (pinfunction "2_2") (pintype "passive"))
      (node (ref "C58") (pin "2") (pinfunction "2_2") (pintype "passive"))
      (node (ref "C59") (pin "1") (pinfunction "1_1") (pintype "passive"))
      (node (ref "C69") (pin "2") (pinfunction "2_2") (pintype "passive"))
      (node (ref "C90") (pin "1") (pinfunction "1_1") (pintype "passive"))
      (node (ref "IC10") (pin "5") (pinfunction "V+_5") (pintype "power_in"))
      (node (ref "IC14") (pin "5") (pinfunction "V+_5") (pintype "power_in"))
      (node (ref "IC38") (pin "5") (pinfunction "VCC_5") (pintype "power_in"))
      (node (ref "IC8") (pin "1") (pinfunction "Vdd_1") (pintype "power_in"))
      (node (ref "IC8") (pin "11") (pinfunction "PVdd2_11") (pintype "power_in"))
      (node (ref "IC8") (pin "18") (pinfunction "PVdd1_18") (pintype "power_in"))
      (node (ref "IC8") (pin "20") (pinfunction "PVdd1_20") (pintype "power_in"))
      (node (ref "IC8") (pin "9") (pinfunction "PVdd2_9") (pintype "power_in"))
    )
    (net (code "43") (name "P5V0A") (class "Default")
      (node (ref "R71") (pin "2") (pinfunction "2_2") (pintype "passive"))
    )
  )
)
